# ModMoPSS_-_IR_sender.net
KiCad netlist of a schematic drawn in EAGLE
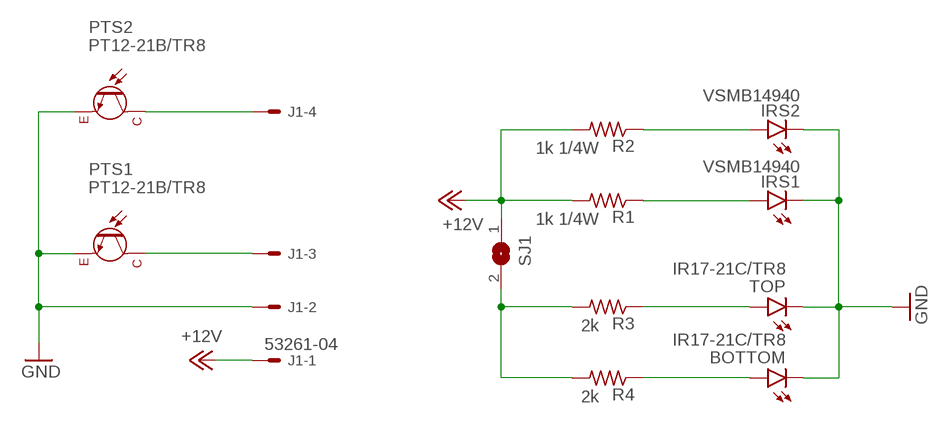
[diagram p0: schematic, sheet 1]

(export (version "E")
  (design (tool "Eeschema 10.0.6"))
  (components
    (comp (ref "BOTTOM")
      (value "IR17-21C/TR8")
      (footprint "eagle-import:CHIP-LED0805")
      (libsource (lib "eagle-import") (part "LEDCHIP-LED0805"))
    )
    (comp (ref "IRS1")
      (value "VSMB14940")
      (footprint "eagle-import:VSMB14940")
      (libsource (lib "eagle-import") (part "VSMB14940"))
    )
    (comp (ref "IRS2")
      (value "VSMB14940")
      (footprint "eagle-import:VSMB14940")
      (libsource (lib "eagle-import") (part "VSMB14940"))
    )
    (comp (ref "J1")
      (value "53261-04")
      (footprint "eagle-import:53261-04")
      (fields (field (name "MF") "MOLEX"))
      (libsource (lib "eagle-import") (part "53?-04261"))
    )
    (comp (ref "PTS1")
      (value "PT12-21B/TR8")
      (footprint "eagle-import:PT12-21B_TR8")
      (libsource (lib "eagle-import") (part "PT12-21B/TR8"))
    )
    (comp (ref "PTS2")
      (value "PT12-21B/TR8")
      (footprint "eagle-import:PT12-21B_TR8")
      (libsource (lib "eagle-import") (part "PT12-21B/TR8"))
    )
    (comp (ref "R1")
      (value "1k 1/4W")
      (footprint "eagle-import:R0805")
      (libsource (lib "eagle-import") (part "R-US_R0805"))
    )
    (comp (ref "R2")
      (value "1k 1/4W")
      (footprint "eagle-import:R0805")
      (libsource (lib "eagle-import") (part "R-US_R0805"))
    )
    (comp (ref "R3")
      (value "2k")
      (footprint "eagle-import:R0805")
      (libsource (lib "eagle-import") (part "R-US_R0805"))
    )
    (comp (ref "R4")
      (value "2k")
      (footprint "eagle-import:R0805")
      (libsource (lib "eagle-import") (part "R-US_R0805"))
    )
    (comp (ref "SJ1") (value "SJ") (footprint "eagle-import:SJ") (libsource (lib "eagle-import") (part "SJ")))
    (comp (ref "TOP")
      (value "IR17-21C/TR8")
      (footprint "eagle-import:CHIP-LED0805")
      (libsource (lib "eagle-import") (part "LEDCHIP-LED0805"))
    )
  )
  (nets
    (net (code "1") (name "+12V") (class "Default")
      (node (ref "J1") (pin "1") (pinfunction "S_1") (pintype "passive"))
      (node (ref "R1") (pin "2") (pinfunction "2_2") (pintype "passive"))
      (node (ref "R2") (pin "2") (pinfunction "2_2") (pintype "passive"))
      (node (ref "SJ1") (pin "1") (pinfunction "1_1") (pintype "passive"))
    )
    (net (code "2") (name "GND") (class "Default")
      (node (ref "BOTTOM") (pin "C") (pinfunction "C_C") (pintype "passive"))
      (node (ref "IRS1") (pin "P$2") (pinfunction "C_P$2") (pintype "passive"))
      (node (ref "IRS2") (pin "P$2") (pinfunction "C_P$2") (pintype "passive"))
      (node (ref "J1") (pin "2") (pinfunction "S_2") (pintype "passive"))
      (node (ref "PTS1") (pin "P$2") (pinfunction "E_P$2") (pintype "passive"))
      (node (ref "PTS2") (pin "P$2") (pinfunction "E_P$2") (pintype "passive"))
      (node (ref "TOP") (pin "C") (pinfunction "C_C") (pintype "passive"))
    )
    (net (code "3") (name "Net-(BOTTOM-PadA)") (class "Default")
      (node (ref "BOTTOM") (pin "A") (pinfunction "A_A") (pintype "passive"))
      (node (ref "R4") (pin "1") (pinfunction "1_1") (pintype "passive"))
    )
    (net (code "4") (name "Net-(IRS1-A)") (class "Default")
      (node (ref "IRS1") (pin "P$1") (pinfunction "A_P$1") (pintype "passive"))
      (node (ref "R1") (pin "1") (pinfunction "1_1") (pintype "passive"))
    )
    (net (code "5") (name "Net-(IRS2-A)") (class "Default")
      (node (ref "IRS2") (pin "P$1") (pinfunction "A_P$1") (pintype "passive"))
      (node (ref "R2") (pin "1") (pinfunction "1_1") (pintype "passive"))
    )
    (net (code "6") (name "Net-(J1C-S)") (class "Default")
      (node (ref "J1") (pin "3") (pinfunction "S_3") (pintype "passive"))
      (node (ref "PTS1") (pin "P$1") (pinfunction "C_P$1") (pintype "passive"))
    )
    (net (code "7") (name "Net-(J1D-S)") (class "Default")
      (node (ref "J1") (pin "4") (pinfunction "S_4") (pintype "passive"))
      (node (ref "PTS2") (pin "P$1") (pinfunction "C_P$1") (pintype "passive"))
    )
    (net (code "8") (name "Net-(R3-Pad1)") (class "Default")
      (node (ref "R3") (pin "1") (pinfunction "1_1") (pintype "passive"))
      (node (ref "TOP") (pin "A") (pinfunction "A_A") (pintype "passive"))
    )
    (net (code "9") (name "Net-(R3-Pad2)") (class "Default")
      (node (ref "R3") (pin "2") (pinfunction "2_2") (pintype "passive"))
      (node (ref "R4") (pin "2") (pinfunction "2_2") (pintype "passive"))
      (node (ref "SJ1") (pin "2") (pinfunction "2_2") (pintype "passive"))
    )
  )
)
